# can.net
KiCad netlist of a schematic drawn in Altium Designer
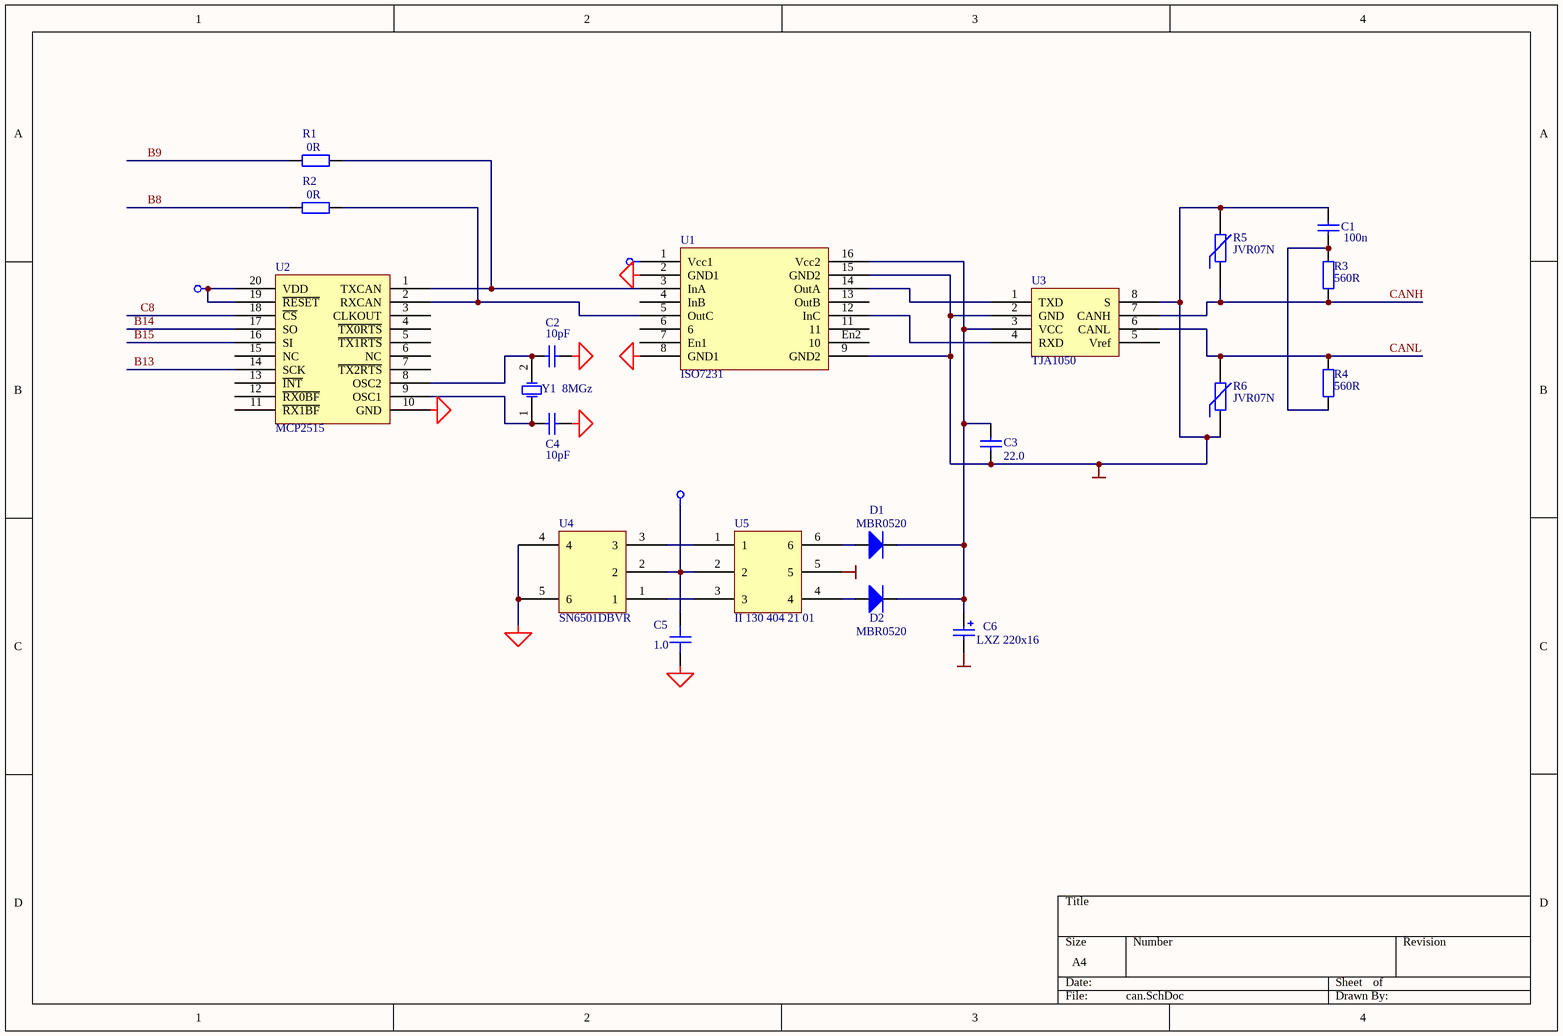
[diagram p0: can.SchDoc]

(export (version "E")
  (design (tool "Eeschema 10.0.6"))
  (components
    (comp (ref "C1")
      (value "100n")
      (footprint "_1206")
      (description "Capacitor (Semiconductor SIM Model)")
      (fields (field (name "MANUFACTURER") "Generic Components") (field (name "PUBLISHER") "Altium Limited"))
      (libsource (lib "Miscellaneous Devices") (part "Cap Semi"))
    )
    (comp (ref "C2")
      (value "10pF")
      (footprint "_1206")
      (description "Capacitor (Semiconductor SIM Model)")
      (fields
        (field (name "MANUFACTURER") "Generic Components")
        (field (name "ALTIUM_VALUE") "10pF")
        (field (name "PUBLISHER") "Altium Limited")
      )
      (libsource (lib "Miscellaneous Devices") (part "Cap Semi"))
    )
    (comp (ref "C3")
      (value "22.0")
      (footprint "_1206")
      (description "Capacitor (Semiconductor SIM Model)")
      (fields (field (name "MANUFACTURER") "Generic Components") (field (name "PUBLISHER") "Altium Limited"))
      (libsource (lib "Miscellaneous Devices") (part "Cap Semi"))
    )
    (comp (ref "C4")
      (value "10pF")
      (footprint "_1206")
      (description "Capacitor (Semiconductor SIM Model)")
      (fields
        (field (name "MANUFACTURER") "Generic Components")
        (field (name "ALTIUM_VALUE") "10pF")
        (field (name "PUBLISHER") "Altium Limited")
      )
      (libsource (lib "Miscellaneous Devices") (part "Cap Semi"))
    )
    (comp (ref "C5") (value "1.0") (footprint "_1206") (libsource (lib "C") (part "C_SM_1206")))
    (comp (ref "C6")
      (value "LXZ 220x16")
      (footprint "el3")
      (description "Polarized Capacitor (Radial)")
      (fields (field (name "MANUFACTURER") "Generic Components") (field (name "PUBLISHER") "Altium Limited"))
      (libsource (lib "PAL") (part "Cap Pol1"))
    )
    (comp (ref "D1")
      (value "MBR0520")
      (footprint "_1206d")
      (description "Default Diode")
      (fields (field (name "MANUFACTURER") "Generic Components") (field (name "PUBLISHER") "Altium Limited"))
      (libsource (lib "PAL") (part "Diode"))
    )
    (comp (ref "D2")
      (value "MBR0520")
      (footprint "_1206d")
      (description "Default Diode")
      (fields (field (name "MANUFACTURER") "Generic Components") (field (name "PUBLISHER") "Altium Limited"))
      (libsource (lib "PAL") (part "Diode"))
    )
    (comp (ref "R1")
      (value "0R")
      (footprint "_1206")
      (description "Resistor")
      (fields (field (name "MANUFACTURER") "Generic Components") (field (name "PUBLISHER") "Altium Limited"))
      (libsource (lib "") (part "Res2_1"))
    )
    (comp (ref "R2")
      (value "0R")
      (footprint "_1206")
      (description "Resistor")
      (fields (field (name "MANUFACTURER") "Generic Components") (field (name "PUBLISHER") "Altium Limited"))
      (libsource (lib "") (part "Res2_1"))
    )
    (comp (ref "R3")
      (value "560R")
      (footprint "_1206")
      (description "Resistor")
      (fields (field (name "MANUFACTURER") "Generic Components") (field (name "PUBLISHER") "Altium Limited"))
      (libsource (lib "Miscellaneous Devices") (part "Res2"))
    )
    (comp (ref "R4")
      (value "560R")
      (footprint "_1206")
      (description "Resistor")
      (fields (field (name "MANUFACTURER") "Generic Components") (field (name "PUBLISHER") "Altium Limited"))
      (libsource (lib "Miscellaneous Devices") (part "Res2"))
    )
    (comp (ref "R5")
      (value "JVR07N")
      (footprint "JVR07N")
      (description "Varistor (Voltage-Sensitive Resistor)")
      (fields (field (name "MANUFACTURER") "Generic Components") (field (name "PUBLISHER") "Altium Limited"))
      (libsource (lib "Miscellaneous Devices") (part "Res Varistor"))
    )
    (comp (ref "R6")
      (value "JVR07N")
      (footprint "JVR07N")
      (description "Varistor (Voltage-Sensitive Resistor)")
      (fields (field (name "MANUFACTURER") "Generic Components") (field (name "PUBLISHER") "Altium Limited"))
      (libsource (lib "Miscellaneous Devices") (part "Res Varistor"))
    )
    (comp (ref "U1") (value "ISO7231") (footprint "SO-G16/D10.4") (libsource (lib "PAL") (part "ISO7231")))
    (comp (ref "U2")
      (value "MCP2515")
      (footprint "TSSO6X6-G20/D6.6")
      (libsource (lib "PAL") (part "MCP2515"))
    )
    (comp (ref "U3") (value "TJA1050") (footprint "SO-G8/D5") (libsource (lib "PAL") (part "TJA1050")))
    (comp (ref "U4") (value "SN6501DBVR") (footprint "SO-G5/P.95") (libsource (lib "CHIP") (part "PIN6")))
    (comp (ref "U5")
      (value "II 130 404 21 01")
      (footprint "II1304042101")
      (libsource (lib "") (part "PIN6_1"))
    )
    (comp (ref "Y1")
      (value "8MGz")
      (footprint "QWARZ1")
      (description "Crystal Oscillator")
      (fields (field (name "MANUFACTURER") "Generic Components") (field (name "PUBLISHER") "Altium Limited"))
      (libsource (lib "Miscellaneous Devices") (part "XTAL"))
    )
  )
  (nets
    (net (code "1") (name "+5v") (class "Default")
      (node (ref "C5") (pin "2") (pinfunction "2_2") (pintype "passive"))
      (node (ref "U1") (pin "1") (pinfunction "Vcc1_1") (pintype "passive"))
      (node (ref "U2") (pin "19") (pinfunction "~{RESET}_19") (pintype "passive"))
      (node (ref "U2") (pin "20") (pinfunction "VDD_20") (pintype "passive"))
      (node (ref "U4") (pin "2") (pinfunction "2_2") (pintype "passive"))
      (node (ref "U5") (pin "2") (pinfunction "2_2") (pintype "passive"))
    )
    (net (code "2") (name "/B8") (class "Default")
      (node (ref "R2") (pin "1") (pinfunction "1_1") (pintype "passive"))
    )
    (net (code "3") (name "/B9") (class "Default")
      (node (ref "R1") (pin "1") (pinfunction "1_1") (pintype "passive"))
    )
    (net (code "4") (name "/B13") (class "Default")
      (node (ref "U2") (pin "14") (pinfunction "SCK_14") (pintype "passive"))
    )
    (net (code "5") (name "/B14") (class "Default")
      (node (ref "U2") (pin "17") (pinfunction "SO_17") (pintype "passive"))
    )
    (net (code "6") (name "/B15") (class "Default")
      (node (ref "U2") (pin "16") (pinfunction "SI_16") (pintype "passive"))
    )
    (net (code "7") (name "/C8") (class "Default")
      (node (ref "U2") (pin "18") (pinfunction "~{CS}_18") (pintype "passive"))
    )
    (net (code "8") (name "/CANH") (class "Default")
      (node (ref "R3") (pin "1") (pinfunction "1_1") (pintype "passive"))
      (node (ref "R5") (pin "1") (pinfunction "1_1") (pintype "passive"))
      (node (ref "U3") (pin "7") (pinfunction "CANH_7") (pintype "passive"))
    )
    (net (code "9") (name "/CANL") (class "Default")
      (node (ref "R4") (pin "2") (pinfunction "2_2") (pintype "passive"))
      (node (ref "R6") (pin "2") (pinfunction "2_2") (pintype "passive"))
      (node (ref "U3") (pin "6") (pinfunction "CANL_6") (pintype "passive"))
    )
    (net (code "10") (name "GND") (class "Default")
      (node (ref "C2") (pin "1") (pinfunction "1_1") (pintype "passive"))
      (node (ref "C4") (pin "1") (pinfunction "1_1") (pintype "passive"))
      (node (ref "C5") (pin "1") (pinfunction "1_1") (pintype "passive"))
      (node (ref "U1") (pin "2") (pinfunction "GND1_2") (pintype "passive"))
      (node (ref "U1") (pin "8") (pinfunction "GND1_8") (pintype "passive"))
      (node (ref "U2") (pin "10") (pinfunction "GND_10") (pintype "passive"))
      (node (ref "U4") (pin "4") (pinfunction "4_4") (pintype "passive"))
      (node (ref "U4") (pin "5") (pinfunction "6_5") (pintype "passive"))
    )
    (net (code "11") (name "GND_CAN") (class "Default")
      (node (ref "C1") (pin "2") (pinfunction "2_2") (pintype "passive"))
      (node (ref "C3") (pin "2") (pinfunction "2_2") (pintype "passive"))
      (node (ref "C6") (pin "2") (pinfunction "2_2") (pintype "passive"))
      (node (ref "R5") (pin "2") (pinfunction "2_2") (pintype "passive"))
      (node (ref "R6") (pin "1") (pinfunction "1_1") (pintype "passive"))
      (node (ref "U1") (pin "15") (pinfunction "GND2_15") (pintype "passive"))
      (node (ref "U1") (pin "9") (pinfunction "GND2_9") (pintype "passive"))
      (node (ref "U3") (pin "2") (pinfunction "GND_2") (pintype "passive"))
      (node (ref "U3") (pin "8") (pinfunction "S_8") (pintype "passive"))
      (node (ref "U5") (pin "5") (pinfunction "5_5") (pintype "passive"))
    )
    (net (code "12") (name "Net-(C1-Pad1)") (class "Default")
      (node (ref "C1") (pin "1") (pinfunction "1_1") (pintype "passive"))
      (node (ref "R3") (pin "2") (pinfunction "2_2") (pintype "passive"))
      (node (ref "R4") (pin "1") (pinfunction "1_1") (pintype "passive"))
    )
    (net (code "13") (name "Net-(D1-A)") (class "Default")
      (node (ref "D1") (pin "1") (pinfunction "A_1") (pintype "passive"))
      (node (ref "U5") (pin "6") (pinfunction "6_6") (pintype "passive"))
    )
    (net (code "14") (name "Net-(D1-K)") (class "Default")
      (node (ref "C3") (pin "1") (pinfunction "1_1") (pintype "passive"))
      (node (ref "C6") (pin "1") (pinfunction "1_1") (pintype "passive"))
      (node (ref "D1") (pin "2") (pinfunction "K_2") (pintype "passive"))
      (node (ref "D2") (pin "2") (pinfunction "K_2") (pintype "passive"))
      (node (ref "U1") (pin "16") (pinfunction "Vcc2_16") (pintype "passive"))
      (node (ref "U3") (pin "3") (pinfunction "VCC_3") (pintype "passive"))
    )
    (net (code "15") (name "Net-(D2-A)") (class "Default")
      (node (ref "D2") (pin "1") (pinfunction "A_1") (pintype "passive"))
      (node (ref "U5") (pin "4") (pinfunction "4_4") (pintype "passive"))
    )
    (net (code "16") (name "Net-(U1-InA)") (class "Default")
      (node (ref "R1") (pin "2") (pinfunction "2_2") (pintype "passive"))
      (node (ref "U1") (pin "3") (pinfunction "InA_3") (pintype "passive"))
      (node (ref "U2") (pin "1") (pinfunction "TXCAN_1") (pintype "passive"))
    )
    (net (code "17") (name "Net-(U1-InC)") (class "Default")
      (node (ref "U1") (pin "12") (pinfunction "InC_12") (pintype "passive"))
      (node (ref "U3") (pin "4") (pinfunction "RXD_4") (pintype "passive"))
    )
    (net (code "18") (name "Net-(U1-OutA)") (class "Default")
      (node (ref "U1") (pin "14") (pinfunction "OutA_14") (pintype "passive"))
      (node (ref "U3") (pin "1") (pinfunction "TXD_1") (pintype "passive"))
    )
    (net (code "19") (name "Net-(U1-OutC)") (class "Default")
      (node (ref "R2") (pin "2") (pinfunction "2_2") (pintype "passive"))
      (node (ref "U1") (pin "5") (pinfunction "OutC_5") (pintype "passive"))
      (node (ref "U2") (pin "2") (pinfunction "RXCAN_2") (pintype "passive"))
    )
    (net (code "20") (name "Net-(U2-OSC1)") (class "Default")
      (node (ref "C4") (pin "2") (pinfunction "2_2") (pintype "passive"))
      (node (ref "U2") (pin "9") (pinfunction "OSC1_9") (pintype "passive"))
      (node (ref "Y1") (pin "1") (pinfunction "OSC1_1") (pintype "passive"))
    )
    (net (code "21") (name "Net-(U2-OSC2)") (class "Default")
      (node (ref "C2") (pin "2") (pinfunction "2_2") (pintype "passive"))
      (node (ref "U2") (pin "8") (pinfunction "OSC2_8") (pintype "passive"))
      (node (ref "Y1") (pin "2") (pinfunction "OSC2_2") (pintype "passive"))
    )
    (net (code "22") (name "Net-(U4-Pad1)") (class "Default")
      (node (ref "U4") (pin "1") (pinfunction "1_1") (pintype "passive"))
      (node (ref "U5") (pin "3") (pinfunction "3_3") (pintype "passive"))
    )
    (net (code "23") (name "Net-(U4-Pad3)") (class "Default")
      (node (ref "U4") (pin "3") (pinfunction "3_3") (pintype "passive"))
      (node (ref "U5") (pin "1") (pinfunction "1_1") (pintype "passive"))
    )
    (net (code "24") (name "unconnected-(U1-10-PadEn2)") (class "Default")
      (node (ref "U1") (pin "En2") (pinfunction "10_En2") (pintype "passive"))
    )
    (net (code "25") (name "unconnected-(U1-En1-Pad7)") (class "Default")
      (node (ref "U1") (pin "7") (pinfunction "En1_7") (pintype "passive"))
    )
    (net (code "26") (name "unconnected-(U1-InB-Pad4)") (class "Default")
      (node (ref "U1") (pin "4") (pinfunction "InB_4") (pintype "passive"))
    )
    (net (code "27") (name "unconnected-(U1-OutB-Pad13)") (class "Default")
      (node (ref "U1") (pin "13") (pinfunction "OutB_13") (pintype "passive"))
    )
    (net (code "28") (name "unconnected-(U1-Pad6)") (class "Default")
      (node (ref "U1") (pin "6") (pinfunction "6_6") (pintype "passive"))
    )
    (net (code "29") (name "unconnected-(U1-Pad11)") (class "Default")
      (node (ref "U1") (pin "11") (pinfunction "11_11") (pintype "passive"))
    )
    (net (code "30") (name "unconnected-(U2-CLKOUT-Pad3)") (class "Default")
      (node (ref "U2") (pin "3") (pinfunction "CLKOUT_3") (pintype "passive"))
    )
    (net (code "31") (name "unconnected-(U2-NC-Pad6)") (class "Default")
      (node (ref "U2") (pin "6") (pinfunction "NC_6") (pintype "passive"))
    )
    (net (code "32") (name "unconnected-(U2-NC-Pad15)") (class "Default")
      (node (ref "U2") (pin "15") (pinfunction "NC_15") (pintype "passive"))
    )
    (net (code "33") (name "unconnected-(U2-~{INT}-Pad13)") (class "Default")
      (node (ref "U2") (pin "13") (pinfunction "~{INT}_13") (pintype "passive"))
    )
    (net (code "34") (name "unconnected-(U2-~{RX0BF}-Pad12)") (class "Default")
      (node (ref "U2") (pin "12") (pinfunction "~{RX0BF}_12") (pintype "passive"))
    )
    (net (code "35") (name "unconnected-(U2-~{RX1BF}-Pad11)") (class "Default")
      (node (ref "U2") (pin "11") (pinfunction "~{RX1BF}_11") (pintype "passive"))
    )
    (net (code "36") (name "unconnected-(U2-~{TX0RTS}-Pad4)") (class "Default")
      (node (ref "U2") (pin "4") (pinfunction "~{TX0RTS}_4") (pintype "passive"))
    )
    (net (code "37") (name "unconnected-(U2-~{TX1RTS}-Pad5)") (class "Default")
      (node (ref "U2") (pin "5") (pinfunction "~{TX1RTS}_5") (pintype "passive"))
    )
    (net (code "38") (name "unconnected-(U2-~{TX2RTS}-Pad7)") (class "Default")
      (node (ref "U2") (pin "7") (pinfunction "~{TX2RTS}_7") (pintype "passive"))
    )
    (net (code "39") (name "unconnected-(U3-Vref-Pad5)") (class "Default")
      (node (ref "U3") (pin "5") (pinfunction "Vref_5") (pintype "passive"))
    )
    (net (code "40") (name "unconnected-(U4-5-Pad6)") (class "Default")
      (node (ref "U4") (pin "6") (pinfunction "5_6") (pintype "passive"))
    )
  )
)
